# Power.net
KiCad netlist of a schematic drawn in Altium Designer
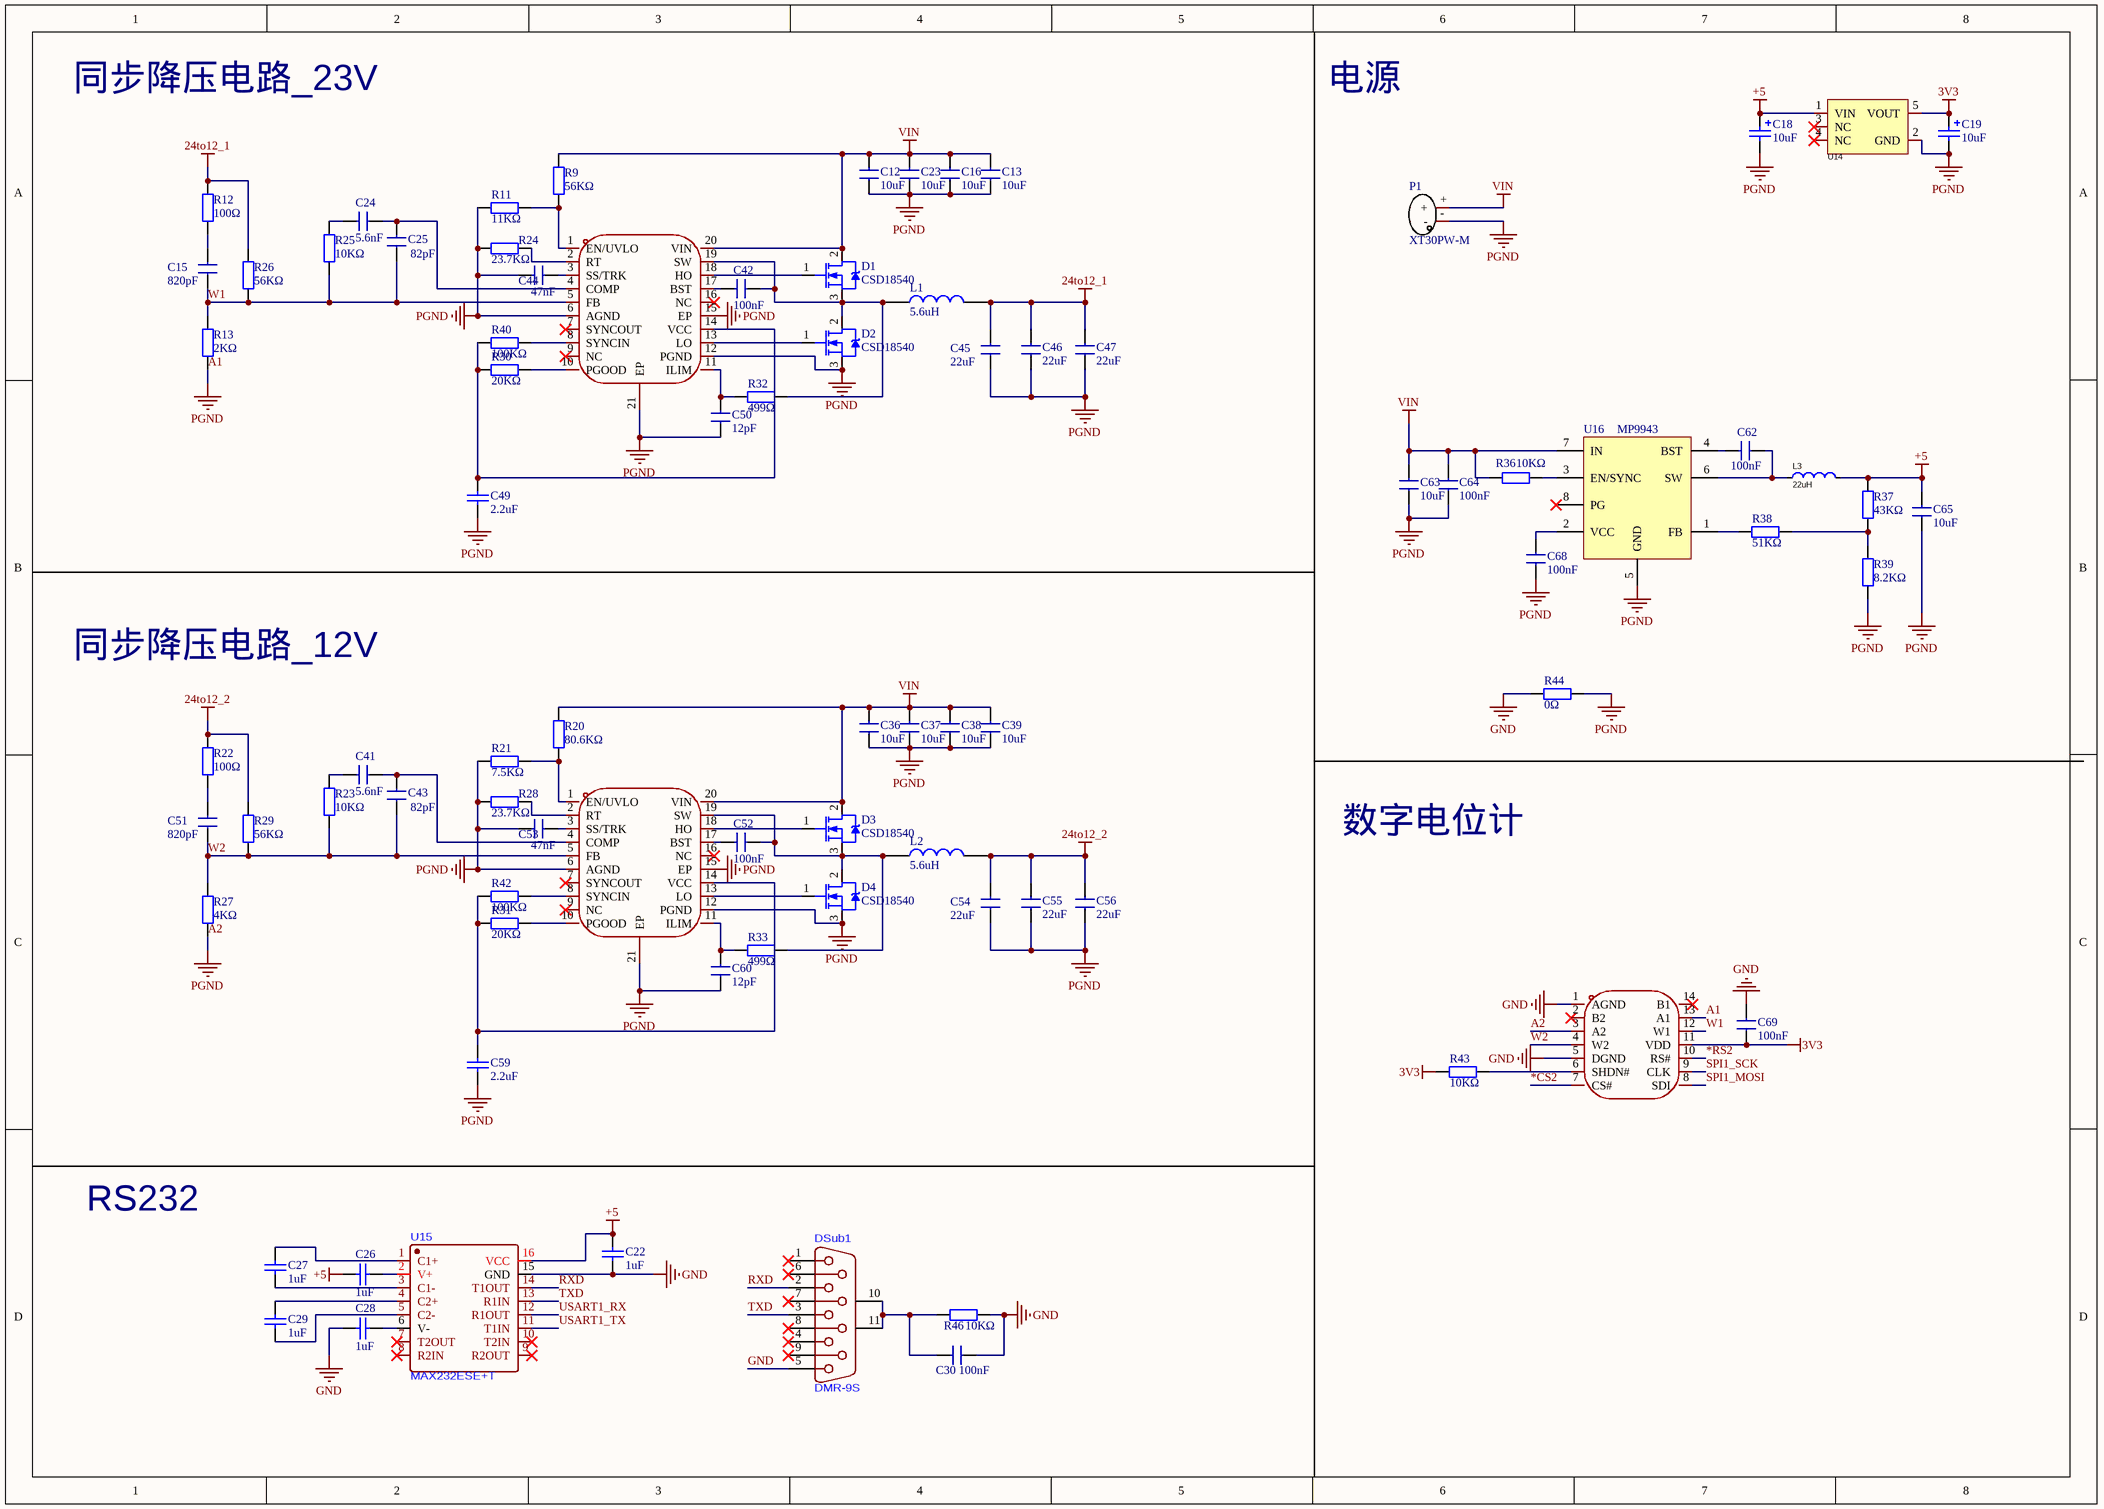
[diagram p0: Power.SchDoc]

(export (version "E")
  (design (tool "Eeschema 10.0.6"))
  (components
    (comp (ref "C12")
      (value "10uF")
      (footprint "1210")
      (description "1210贴片电容")
      (libsource (lib "Integrated_Library1") (part "1210贴片电容"))
    )
    (comp (ref "C13")
      (value "10uF")
      (footprint "1210")
      (description "1210贴片电容")
      (libsource (lib "En") (part "1210贴片电容"))
    )
    (comp (ref "C15")
      (value "820pF")
      (footprint "c0402")
      (description "贴片电容0402")
      (libsource (lib "Integrated_Library1") (part "0402贴片电容"))
    )
    (comp (ref "C16")
      (value "10uF")
      (footprint "1210")
      (description "1210贴片电容")
      (libsource (lib "En") (part "1210贴片电容"))
    )
    (comp (ref "C18")
      (value "10uF")
      (footprint "3216")
      (description "3216钽电容")
      (libsource (lib "Integrated_Library1") (part "3216钽电容"))
    )
    (comp (ref "C19")
      (value "10uF")
      (footprint "3216")
      (description "3216钽电容")
      (libsource (lib "Integrated_Library1") (part "3216钽电容"))
    )
    (comp (ref "C22")
      (value "1uF")
      (footprint "C 0603_M")
      (description "0603贴片电容")
      (libsource (lib "En") (part "0603贴片电容"))
    )
    (comp (ref "C23")
      (value "10uF")
      (footprint "1210")
      (description "1210贴片电容")
      (libsource (lib "En") (part "1210贴片电容"))
    )
    (comp (ref "C24")
      (value "5.6nF")
      (footprint "c0402")
      (description "贴片电容0402")
      (libsource (lib "Integrated_Library1") (part "0402贴片电容"))
    )
    (comp (ref "C25")
      (value "82pF")
      (footprint "c0402")
      (description "贴片电容0402")
      (libsource (lib "Integrated_Library1") (part "0402贴片电容"))
    )
    (comp (ref "C26")
      (value "1uF")
      (footprint "C 0603_M")
      (description "0603贴片电容")
      (libsource (lib "En") (part "0603贴片电容"))
    )
    (comp (ref "C27")
      (value "1uF")
      (footprint "C 0603_M")
      (description "0603贴片电容")
      (libsource (lib "En") (part "0603贴片电容"))
    )
    (comp (ref "C28")
      (value "1uF")
      (footprint "C 0603_M")
      (description "0603贴片电容")
      (libsource (lib "En") (part "0603贴片电容"))
    )
    (comp (ref "C29")
      (value "1uF")
      (footprint "C 0603_M")
      (description "0603贴片电容")
      (libsource (lib "En") (part "0603贴片电容"))
    )
    (comp (ref "C30")
      (value "100nF")
      (footprint "c0402")
      (description "贴片电容0402")
      (libsource (lib "Integrated_Library1") (part "0402贴片电容"))
    )
    (comp (ref "C36")
      (value "10uF")
      (footprint "1210")
      (description "1210贴片电容")
      (libsource (lib "Integrated_Library1") (part "1210贴片电容"))
    )
    (comp (ref "C37")
      (value "10uF")
      (footprint "1210")
      (description "1210贴片电容")
      (libsource (lib "En") (part "1210贴片电容"))
    )
    (comp (ref "C38")
      (value "10uF")
      (footprint "1210")
      (description "1210贴片电容")
      (libsource (lib "En") (part "1210贴片电容"))
    )
    (comp (ref "C39")
      (value "10uF")
      (footprint "1210")
      (description "1210贴片电容")
      (libsource (lib "En") (part "1210贴片电容"))
    )
    (comp (ref "C41")
      (value "5.6nF")
      (footprint "c0402")
      (description "贴片电容0402")
      (libsource (lib "Integrated_Library1") (part "0402贴片电容"))
    )
    (comp (ref "C42")
      (value "100nF")
      (footprint "C 0603_M")
      (description "贴片电容0402")
      (libsource (lib "Integrated_Library1") (part "0402贴片电容"))
    )
    (comp (ref "C43")
      (value "82pF")
      (footprint "c0402")
      (description "贴片电容0402")
      (libsource (lib "Integrated_Library1") (part "0402贴片电容"))
    )
    (comp (ref "C44")
      (value "47nF")
      (footprint "c0402")
      (description "贴片电容0402")
      (libsource (lib "Integrated_Library1") (part "0402贴片电容"))
    )
    (comp (ref "C45")
      (value "22uF")
      (footprint "1210")
      (description "1210贴片电容")
      (libsource (lib "En") (part "1210贴片电容"))
    )
    (comp (ref "C46")
      (value "22uF")
      (footprint "1210")
      (description "1210贴片电容")
      (libsource (lib "En") (part "1210贴片电容"))
    )
    (comp (ref "C47")
      (value "22uF")
      (footprint "1210")
      (description "1210贴片电容")
      (libsource (lib "En") (part "1210贴片电容"))
    )
    (comp (ref "C49")
      (value "2.2uF")
      (footprint "C 0603_M")
      (description "0603贴片电容")
      (libsource (lib "En") (part "0603贴片电容"))
    )
    (comp (ref "C50")
      (value "12pF")
      (footprint "c0402")
      (description "贴片电容0402")
      (libsource (lib "Integrated_Library1") (part "0402贴片电容"))
    )
    (comp (ref "C51")
      (value "820pF")
      (footprint "c0402")
      (description "贴片电容0402")
      (libsource (lib "Integrated_Library1") (part "0402贴片电容"))
    )
    (comp (ref "C52")
      (value "100nF")
      (footprint "C 0603_M")
      (description "贴片电容0402")
      (libsource (lib "Integrated_Library1") (part "0402贴片电容"))
    )
    (comp (ref "C53")
      (value "47nF")
      (footprint "c0402")
      (description "贴片电容0402")
      (libsource (lib "Integrated_Library1") (part "0402贴片电容"))
    )
    (comp (ref "C54")
      (value "22uF")
      (footprint "1210")
      (description "1210贴片电容")
      (libsource (lib "En") (part "1210贴片电容"))
    )
    (comp (ref "C55")
      (value "22uF")
      (footprint "1210")
      (description "1210贴片电容")
      (libsource (lib "En") (part "1210贴片电容"))
    )
    (comp (ref "C56")
      (value "22uF")
      (footprint "1210")
      (description "1210贴片电容")
      (libsource (lib "En") (part "1210贴片电容"))
    )
    (comp (ref "C59")
      (value "2.2uF")
      (footprint "C 0603_M")
      (description "0603贴片电容")
      (libsource (lib "En") (part "0603贴片电容"))
    )
    (comp (ref "C60")
      (value "12pF")
      (footprint "c0402")
      (description "贴片电容0402")
      (libsource (lib "Integrated_Library1") (part "0402贴片电容"))
    )
    (comp (ref "C62")
      (value "100nF")
      (footprint "c0402")
      (description "贴片电容0402")
      (libsource (lib "Integrated_Library1") (part "0402贴片电容"))
    )
    (comp (ref "C63")
      (value "10uF")
      (footprint "1210")
      (description "1210贴片电容")
      (libsource (lib "Integrated_Library1") (part "1210贴片电容"))
    )
    (comp (ref "C64")
      (value "100nF")
      (footprint "c0402")
      (description "贴片电容0402")
      (libsource (lib "Integrated_Library1") (part "0402贴片电容"))
    )
    (comp (ref "C65")
      (value "10uF")
      (footprint "1210")
      (description "1210贴片电容")
      (libsource (lib "Integrated_Library1") (part "1210贴片电容"))
    )
    (comp (ref "C68")
      (value "100nF")
      (footprint "c0402")
      (description "贴片电容0402")
      (libsource (lib "Integrated_Library1") (part "0402贴片电容"))
    )
    (comp (ref "C69")
      (value "100nF")
      (footprint "c0402")
      (description "贴片电容0402")
      (libsource (lib "Integrated_Library1") (part "0402贴片电容"))
    )
    (comp (ref "D1")
      (value "CSD18540")
      (footprint "pg-tdson-8")
      (description "N沟道MOS管")
      (fields (field (name "PUBLISHER") "Altium Limited"))
      (libsource (lib "En") (part "CSD18540"))
    )
    (comp (ref "D2")
      (value "CSD18540")
      (footprint "pg-tdson-8")
      (description "N沟道MOS管")
      (fields (field (name "PUBLISHER") "Altium Limited"))
      (libsource (lib "En") (part "CSD18540"))
    )
    (comp (ref "D3")
      (value "CSD18540")
      (footprint "pg-tdson-8")
      (description "N沟道MOS管")
      (fields (field (name "PUBLISHER") "Altium Limited"))
      (libsource (lib "En") (part "CSD18540"))
    )
    (comp (ref "D4")
      (value "CSD18540")
      (footprint "pg-tdson-8")
      (description "N沟道MOS管")
      (fields (field (name "PUBLISHER") "Altium Limited"))
      (libsource (lib "En") (part "CSD18540"))
    )
    (comp (ref "DSub1")
      (value "DMR-9S")
      (footprint "DSUB-TH_DMR-9S")
      (libsource (lib "Schlib1") (part "DMR-9S"))
    )
    (comp (ref "L1")
      (value "5.6uH")
      (footprint "L-SMD-0630")
      (description "一体成型屏蔽电感")
      (libsource (lib "En") (part "0630功率电感"))
    )
    (comp (ref "L2")
      (value "5.6uH")
      (footprint "L-SMD-0630")
      (description "一体成型屏蔽电感")
      (libsource (lib "En") (part "0630功率电感"))
    )
    (comp (ref "L3")
      (value "22uH")
      (footprint "IND-SMD_L5.4-W5.2")
      (description "一体成型屏蔽电感，0530封装，额定电流3A")
      (fields (field (name "MANUFACTURER") "XR(祥如)") (field (name "MANUFACTURER PART") "XR0530-100M"))
      (libsource (lib "En") (part "0530屏蔽电感"))
    )
    (comp (ref "P1")
      (value "XT30PW-M")
      (footprint "XT30PW-M")
      (description "卧式XT30母头")
      (fields (field (name "PUBLISHER") "Altium Limited"))
      (libsource (lib "Integrated_Library1") (part "卧式XT30母头"))
    )
    (comp (ref "R9")
      (value "56KΩ")
      (footprint "R0402")
      (description "0402贴片电阻")
      (libsource (lib "Integrated_Library1") (part "0402贴片电阻"))
    )
    (comp (ref "R11")
      (value "11KΩ")
      (footprint "R0402")
      (description "0402贴片电阻")
      (libsource (lib "") (part "0402贴片电阻_3"))
    )
    (comp (ref "R12")
      (value "100Ω")
      (footprint "R0402")
      (description "0402贴片电阻")
      (libsource (lib "") (part "0402贴片电阻_1"))
    )
    (comp (ref "R13")
      (value "2KΩ")
      (footprint "R0402")
      (description "0402贴片电阻")
      (libsource (lib "Integrated_Library1") (part "0402贴片电阻"))
    )
    (comp (ref "R20")
      (value "80.6KΩ")
      (footprint "R0402")
      (description "0402贴片电阻")
      (libsource (lib "Integrated_Library1") (part "0402贴片电阻"))
    )
    (comp (ref "R21")
      (value "7.5KΩ")
      (footprint "R0402")
      (description "0402贴片电阻")
      (libsource (lib "") (part "0402贴片电阻_3"))
    )
    (comp (ref "R22")
      (value "100Ω")
      (footprint "R0402")
      (description "0402贴片电阻")
      (libsource (lib "") (part "0402贴片电阻_1"))
    )
    (comp (ref "R23")
      (value "10KΩ")
      (footprint "R0402")
      (description "0402贴片电阻")
      (libsource (lib "") (part "0402贴片电阻_1"))
    )
    (comp (ref "R24")
      (value "23.7KΩ")
      (footprint "R0402")
      (description "0402贴片电阻")
      (libsource (lib "") (part "0402贴片电阻_2"))
    )
    (comp (ref "R25")
      (value "10KΩ")
      (footprint "R0402")
      (description "0402贴片电阻")
      (libsource (lib "") (part "0402贴片电阻_1"))
    )
    (comp (ref "R26")
      (value "56KΩ")
      (footprint "R0402")
      (description "0402贴片电阻")
      (libsource (lib "") (part "0402贴片电阻_1"))
    )
    (comp (ref "R27")
      (value "4KΩ")
      (footprint "R0402")
      (description "0402贴片电阻")
      (libsource (lib "Integrated_Library1") (part "0402贴片电阻"))
    )
    (comp (ref "R28")
      (value "23.7KΩ")
      (footprint "R0402")
      (description "0402贴片电阻")
      (libsource (lib "") (part "0402贴片电阻_2"))
    )
    (comp (ref "R29")
      (value "56KΩ")
      (footprint "R0402")
      (description "0402贴片电阻")
      (libsource (lib "") (part "0402贴片电阻_1"))
    )
    (comp (ref "R30")
      (value "20KΩ")
      (footprint "R0402")
      (description "0402贴片电阻")
      (libsource (lib "") (part "0402贴片电阻_2"))
    )
    (comp (ref "R31")
      (value "20KΩ")
      (footprint "R0402")
      (description "0402贴片电阻")
      (libsource (lib "") (part "0402贴片电阻_2"))
    )
    (comp (ref "R32")
      (value "499Ω")
      (footprint "R0402")
      (description "0402贴片电阻")
      (libsource (lib "") (part "0402贴片电阻_2"))
    )
    (comp (ref "R33")
      (value "499Ω")
      (footprint "R0402")
      (description "0402贴片电阻")
      (libsource (lib "") (part "0402贴片电阻_2"))
    )
    (comp (ref "R36")
      (value "10KΩ")
      (footprint "R0402")
      (description "0402贴片电阻")
      (libsource (lib "") (part "0402贴片电阻_3"))
    )
    (comp (ref "R37")
      (value "43KΩ")
      (footprint "R0402")
      (description "0402贴片电阻")
      (libsource (lib "") (part "0402贴片电阻_1"))
    )
    (comp (ref "R38")
      (value "51KΩ")
      (footprint "R0402")
      (description "0402贴片电阻")
      (libsource (lib "") (part "0402贴片电阻_3"))
    )
    (comp (ref "R39")
      (value "8.2KΩ")
      (footprint "R0402")
      (description "0402贴片电阻")
      (libsource (lib "") (part "0402贴片电阻_1"))
    )
    (comp (ref "R40")
      (value "100KΩ")
      (footprint "R0402")
      (description "0402贴片电阻")
      (libsource (lib "") (part "0402贴片电阻_2"))
    )
    (comp (ref "R42")
      (value "100KΩ")
      (footprint "R0402")
      (description "0402贴片电阻")
      (libsource (lib "") (part "0402贴片电阻_2"))
    )
    (comp (ref "R43")
      (value "10KΩ")
      (footprint "R0402")
      (description "0402贴片电阻")
      (libsource (lib "") (part "0402贴片电阻_2"))
    )
    (comp (ref "R44")
      (value "0Ω")
      (footprint "R0402")
      (description "0402贴片电阻")
      (libsource (lib "") (part "0402贴片电阻_3"))
    )
    (comp (ref "R46")
      (value "10KΩ")
      (footprint "R0402")
      (description "0402贴片电阻")
      (libsource (lib "") (part "0402贴片电阻_4"))
    )
    (comp (ref "U7")
      (value "LM25145RGYR")
      (footprint "VQFN-20_L4.5-W3.5-P0.50-BL-EP")
      (fields (field (name "MANUFACTURER") "TI(德州仪器)"))
      (libsource (lib "Schlib1") (part "LM25145RGYR"))
    )
    (comp (ref "U13")
      (value "LM25145RGYR")
      (footprint "VQFN-20_L4.5-W3.5-P0.50-BL-EP")
      (fields (field (name "MANUFACTURER") "TI(德州仪器)"))
      (libsource (lib "Schlib1") (part "LM25145RGYR"))
    )
    (comp (ref "U14")
      (value "XC6201P332MR-HXY")
      (footprint "SOT-23-5_L3.0-W1.7-P0.95-LS2.8-BR")
      (description "3.3V LDO")
      (fields (field (name "MANUFACTURER") "HXY MOSFET(华轩阳电子)"))
      (libsource (lib "Integrated_Library1") (part "XC6201P332MR-HXY"))
    )
    (comp (ref "U15")
      (value "MAX232ESE+T")
      (footprint "SOIC-16_L9.9-W3.9-P1.27-LS6.0-BL")
      (libsource (lib "Schlib1") (part "MAX232ESE+T"))
    )
    (comp (ref "U16")
      (value "MP9943")
      (footprint "QFN-8 3x3")
      (libsource (lib "Integrated_Library1") (part "MP9943"))
    )
    (comp (ref "U17")
      (value "AD8402ARZ10-REEL")
      (footprint "SOIC-14_L8.7-W3.9-P1.27-LS6.0-BL")
      (fields (field (name "MANUFACTURER") "ADI(亚德诺)"))
      (libsource (lib "Schlib1") (part "AD8402ARZ10-REEL"))
    )
  )
  (nets
    (net (code "1") (name "+5") (class "Default")
      (node (ref "C18") (pin "1") (pinfunction "1_1") (pintype "passive"))
      (node (ref "C22") (pin "2") (pinfunction "2_2") (pintype "passive"))
      (node (ref "C26") (pin "2") (pinfunction "2_2") (pintype "passive"))
      (node (ref "C65") (pin "2") (pinfunction "2_2") (pintype "passive"))
      (node (ref "L3") (pin "2") (pinfunction "2_2") (pintype "passive"))
      (node (ref "R37") (pin "2") (pinfunction "2_2") (pintype "passive"))
      (node (ref "U14") (pin "1") (pinfunction "VIN_1") (pintype "passive"))
      (node (ref "U15") (pin "16") (pinfunction "VCC_16") (pintype "passive"))
    )
    (net (code "2") (name "/*CS2") (class "Default")
      (node (ref "U17") (pin "7") (pinfunction "CS#_7") (pintype "passive"))
    )
    (net (code "3") (name "/*RS2") (class "Default")
      (node (ref "U17") (pin "10") (pinfunction "RS#_10") (pintype "passive"))
    )
    (net (code "4") (name "/RXD") (class "Default")
      (node (ref "DSub1") (pin "2") (pinfunction "2_2") (pintype "passive"))
      (node (ref "U15") (pin "14") (pinfunction "T1OUT_14") (pintype "passive"))
    )
    (net (code "5") (name "/SPI1_MOSI") (class "Default")
      (node (ref "U17") (pin "8") (pinfunction "SDI_8") (pintype "passive"))
    )
    (net (code "6") (name "/SPI1_SCK") (class "Default")
      (node (ref "U17") (pin "9") (pinfunction "CLK_9") (pintype "passive"))
    )
    (net (code "7") (name "/TXD") (class "Default")
      (node (ref "DSub1") (pin "3") (pinfunction "3_3") (pintype "passive"))
      (node (ref "U15") (pin "13") (pinfunction "R1IN_13") (pintype "passive"))
    )
    (net (code "8") (name "/USART1_RX") (class "Default")
      (node (ref "U15") (pin "12") (pinfunction "R1OUT_12") (pintype "passive"))
    )
    (net (code "9") (name "/USART1_TX") (class "Default")
      (node (ref "U15") (pin "11") (pinfunction "T1IN_11") (pintype "passive"))
    )
    (net (code "10") (name "/W1") (class "Default")
      (node (ref "C15") (pin "2") (pinfunction "2_2") (pintype "passive"))
      (node (ref "C25") (pin "1") (pinfunction "1_1") (pintype "passive"))
      (node (ref "R13") (pin "1") (pinfunction "1_1") (pintype "passive"))
      (node (ref "R25") (pin "1") (pinfunction "1_1") (pintype "passive"))
      (node (ref "R26") (pin "1") (pinfunction "1_1") (pintype "passive"))
      (node (ref "U13") (pin "5") (pinfunction "FB_5") (pintype "passive"))
      (node (ref "U17") (pin "12") (pinfunction "W1_12") (pintype "passive"))
    )
    (net (code "11") (name "/W2") (class "Default")
      (node (ref "C43") (pin "1") (pinfunction "1_1") (pintype "passive"))
      (node (ref "C51") (pin "2") (pinfunction "2_2") (pintype "passive"))
      (node (ref "R23") (pin "1") (pinfunction "1_1") (pintype "passive"))
      (node (ref "R27") (pin "1") (pinfunction "1_1") (pintype "passive"))
      (node (ref "R29") (pin "1") (pinfunction "1_1") (pintype "passive"))
      (node (ref "U17") (pin "4") (pinfunction "W2_4") (pintype "passive"))
      (node (ref "U7") (pin "5") (pinfunction "FB_5") (pintype "passive"))
    )
    (net (code "12") (name "3V3") (class "Default")
      (node (ref "C19") (pin "1") (pinfunction "1_1") (pintype "passive"))
      (node (ref "C69") (pin "2") (pinfunction "2_2") (pintype "passive"))
      (node (ref "R43") (pin "2") (pinfunction "2_2") (pintype "passive"))
      (node (ref "U14") (pin "5") (pinfunction "VOUT_5") (pintype "passive"))
      (node (ref "U17") (pin "11") (pinfunction "VDD_11") (pintype "passive"))
    )
    (net (code "13") (name "24to12_1") (class "Default")
      (node (ref "C45") (pin "2") (pinfunction "2_2") (pintype "passive"))
      (node (ref "C46") (pin "2") (pinfunction "2_2") (pintype "passive"))
      (node (ref "C47") (pin "2") (pinfunction "2_2") (pintype "passive"))
      (node (ref "L1") (pin "2") (pinfunction "2_2") (pintype "passive"))
      (node (ref "R12") (pin "2") (pinfunction "2_2") (pintype "passive"))
      (node (ref "R26") (pin "2") (pinfunction "2_2") (pintype "passive"))
    )
    (net (code "14") (name "24to12_2") (class "Default")
      (node (ref "C54") (pin "2") (pinfunction "2_2") (pintype "passive"))
      (node (ref "C55") (pin "2") (pinfunction "2_2") (pintype "passive"))
      (node (ref "C56") (pin "2") (pinfunction "2_2") (pintype "passive"))
      (node (ref "L2") (pin "2") (pinfunction "2_2") (pintype "passive"))
      (node (ref "R22") (pin "2") (pinfunction "2_2") (pintype "passive"))
      (node (ref "R29") (pin "2") (pinfunction "2_2") (pintype "passive"))
    )
    (net (code "15") (name "GND") (class "Default")
      (node (ref "C22") (pin "1") (pinfunction "1_1") (pintype "passive"))
      (node (ref "C28") (pin "2") (pinfunction "2_2") (pintype "passive"))
      (node (ref "C30") (pin "2") (pinfunction "2_2") (pintype "passive"))
      (node (ref "C69") (pin "1") (pinfunction "1_1") (pintype "passive"))
      (node (ref "DSub1") (pin "5") (pinfunction "5_5") (pintype "passive"))
      (node (ref "R44") (pin "1") (pinfunction "1_1") (pintype "passive"))
      (node (ref "R46") (pin "2") (pinfunction "2_2") (pintype "passive"))
      (node (ref "U15") (pin "15") (pinfunction "GND_15") (pintype "passive"))
      (node (ref "U17") (pin "1") (pinfunction "AGND_1") (pintype "passive"))
      (node (ref "U17") (pin "5") (pinfunction "DGND_5") (pintype "passive"))
    )
    (net (code "16") (name "Net-(C15-Pad1)") (class "Default")
      (node (ref "C15") (pin "1") (pinfunction "1_1") (pintype "passive"))
      (node (ref "R12") (pin "1") (pinfunction "1_1") (pintype "passive"))
    )
    (net (code "17") (name "Net-(C24-Pad2)") (class "Default")
      (node (ref "C24") (pin "2") (pinfunction "2_2") (pintype "passive"))
      (node (ref "R25") (pin "2") (pinfunction "2_2") (pintype "passive"))
    )
    (net (code "18") (name "Net-(C41-Pad2)") (class "Default")
      (node (ref "C41") (pin "2") (pinfunction "2_2") (pintype "passive"))
      (node (ref "R23") (pin "2") (pinfunction "2_2") (pintype "passive"))
    )
    (net (code "19") (name "Net-(C51-Pad1)") (class "Default")
      (node (ref "C51") (pin "1") (pinfunction "1_1") (pintype "passive"))
      (node (ref "R22") (pin "1") (pinfunction "1_1") (pintype "passive"))
    )
    (net (code "20") (name "Net-(D1-G)") (class "Default")
      (node (ref "D1") (pin "1") (pinfunction "G_1") (pintype "passive"))
      (node (ref "U13") (pin "18") (pinfunction "HO_18") (pintype "passive"))
    )
    (net (code "21") (name "Net-(D1-S)") (class "Default")
      (node (ref "C42") (pin "1") (pinfunction "1_1") (pintype "passive"))
      (node (ref "D1") (pin "3") (pinfunction "S_3") (pintype "passive"))
      (node (ref "D2") (pin "2") (pinfunction "D_2") (pintype "passive"))
      (node (ref "L1") (pin "1") (pinfunction "1_1") (pintype "passive"))
      (node (ref "R32") (pin "1") (pinfunction "1_1") (pintype "passive"))
      (node (ref "U13") (pin "19") (pinfunction "SW_19") (pintype "passive"))
    )
    (net (code "22") (name "Net-(D2-G)") (class "Default")
      (node (ref "D2") (pin "1") (pinfunction "G_1") (pintype "passive"))
      (node (ref "U13") (pin "13") (pinfunction "LO_13") (pintype "passive"))
    )
    (net (code "23") (name "Net-(D3-G)") (class "Default")
      (node (ref "D3") (pin "1") (pinfunction "G_1") (pintype "passive"))
      (node (ref "U7") (pin "18") (pinfunction "HO_18") (pintype "passive"))
    )
    (net (code "24") (name "Net-(D3-S)") (class "Default")
      (node (ref "C52") (pin "1") (pinfunction "1_1") (pintype "passive"))
      (node (ref "D3") (pin "3") (pinfunction "S_3") (pintype "passive"))
      (node (ref "D4") (pin "2") (pinfunction "D_2") (pintype "passive"))
      (node (ref "L2") (pin "1") (pinfunction "1_1") (pintype "passive"))
      (node (ref "R33") (pin "1") (pinfunction "1_1") (pintype "passive"))
      (node (ref "U7") (pin "19") (pinfunction "SW_19") (pintype "passive"))
    )
    (net (code "25") (name "Net-(D4-G)") (class "Default")
      (node (ref "D4") (pin "1") (pinfunction "G_1") (pintype "passive"))
      (node (ref "U7") (pin "13") (pinfunction "LO_13") (pintype "passive"))
    )
    (net (code "26") (name "Net-(DSub1-MH1)") (class "Default")
      (node (ref "C30") (pin "1") (pinfunction "1_1") (pintype "passive"))
      (node (ref "DSub1") (pin "10") (pinfunction "MH1_10") (pintype "passive"))
      (node (ref "DSub1") (pin "11") (pinfunction "MH2_11") (pintype "passive"))
      (node (ref "R46") (pin "1") (pinfunction "1_1") (pintype "passive"))
    )
    (net (code "27") (name "Net-(R37-Pad1)") (class "Default")
      (node (ref "R37") (pin "1") (pinfunction "1_1") (pintype "passive"))
      (node (ref "R38") (pin "2") (pinfunction "2_2") (pintype "passive"))
      (node (ref "R39") (pin "2") (pinfunction "2_2") (pintype "passive"))
    )
    (net (code "28") (name "Net-(U7-BST)") (class "Default")
      (node (ref "C52") (pin "2") (pinfunction "2_2") (pintype "passive"))
      (node (ref "U7") (pin "17") (pinfunction "BST_17") (pintype "passive"))
    )
    (net (code "29") (name "Net-(U7-COMP)") (class "Default")
      (node (ref "C41") (pin "1") (pinfunction "1_1") (pintype "passive"))
      (node (ref "C43") (pin "2") (pinfunction "2_2") (pintype "passive"))
      (node (ref "U7") (pin "4") (pinfunction "COMP_4") (pintype "passive"))
    )
    (net (code "30") (name "Net-(U7-EN{slash}UVLO)") (class "Default")
      (node (ref "R20") (pin "2") (pinfunction "2_2") (pintype "passive"))
      (node (ref "R21") (pin "2") (pinfunction "2_2") (pintype "passive"))
      (node (ref "U7") (pin "1") (pinfunction "EN/UVLO_1") (pintype "passive"))
    )
    (net (code "31") (name "Net-(U7-ILIM)") (class "Default")
      (node (ref "C60") (pin "2") (pinfunction "2_2") (pintype "passive"))
      (node (ref "R33") (pin "2") (pinfunction "2_2") (pintype "passive"))
      (node (ref "U7") (pin "11") (pinfunction "ILIM_11") (pintype "passive"))
    )
    (net (code "32") (name "Net-(U7-PGOOD)") (class "Default")
      (node (ref "R31") (pin "1") (pinfunction "1_1") (pintype "passive"))
      (node (ref "U7") (pin "10") (pinfunction "PGOOD_10") (pintype "passive"))
    )
    (net (code "33") (name "Net-(U7-RT)") (class "Default")
      (node (ref "R28") (pin "1") (pinfunction "1_1") (pintype "passive"))
      (node (ref "U7") (pin "2") (pinfunction "RT_2") (pintype "passive"))
    )
    (net (code "34") (name "Net-(U7-SS{slash}TRK)") (class "Default")
      (node (ref "C53") (pin "1") (pinfunction "1_1") (pintype "passive"))
      (node (ref "U7") (pin "3") (pinfunction "SS/TRK_3") (pintype "passive"))
    )
    (net (code "35") (name "Net-(U7-SYNCIN)") (class "Default")
      (node (ref "R42") (pin "1") (pinfunction "1_1") (pintype "passive"))
      (node (ref "U7") (pin "8") (pinfunction "SYNCIN_8") (pintype "passive"))
    )
    (net (code "36") (name "Net-(U7-VCC)") (class "Default")
      (node (ref "C59") (pin "2") (pinfunction "2_2") (pintype "passive"))
      (node (ref "R31") (pin "2") (pinfunction "2_2") (pintype "passive"))
      (node (ref "R42") (pin "2") (pinfunction "2_2") (pintype "passive"))
      (node (ref "U7") (pin "14") (pinfunction "VCC_14") (pintype "passive"))
    )
    (net (code "37") (name "Net-(U13-BST)") (class "Default")
      (node (ref "C42") (pin "2") (pinfunction "2_2") (pintype "passive"))
      (node (ref "U13") (pin "17") (pinfunction "BST_17") (pintype "passive"))
    )
    (net (code "38") (name "Net-(U13-COMP)") (class "Default")
      (node (ref "C24") (pin "1") (pinfunction "1_1") (pintype "passive"))
      (node (ref "C25") (pin "2") (pinfunction "2_2") (pintype "passive"))
      (node (ref "U13") (pin "4") (pinfunction "COMP_4") (pintype "passive"))
    )
    (net (code "39") (name "Net-(U13-EN{slash}UVLO)") (class "Default")
      (node (ref "R11") (pin "2") (pinfunction "2_2") (pintype "passive"))
      (node (ref "R9") (pin "2") (pinfunction "2_2") (pintype "passive"))
      (node (ref "U13") (pin "1") (pinfunction "EN/UVLO_1") (pintype "passive"))
    )
    (net (code "40") (name "Net-(U13-ILIM)") (class "Default")
      (node (ref "C50") (pin "2") (pinfunction "2_2") (pintype "passive"))
      (node (ref "R32") (pin "2") (pinfunction "2_2") (pintype "passive"))
      (node (ref "U13") (pin "11") (pinfunction "ILIM_11") (pintype "passive"))
    )
    (net (code "41") (name "Net-(U13-PGOOD)") (class "Default")
      (node (ref "R30") (pin "1") (pinfunction "1_1") (pintype "passive"))
      (node (ref "U13") (pin "10") (pinfunction "PGOOD_10") (pintype "passive"))
    )
    (net (code "42") (name "Net-(U13-RT)") (class "Default")
      (node (ref "R24") (pin "1") (pinfunction "1_1") (pintype "passive"))
      (node (ref "U13") (pin "2") (pinfunction "RT_2") (pintype "passive"))
    )
    (net (code "43") (name "Net-(U13-SS{slash}TRK)") (class "Default")
      (node (ref "C44") (pin "1") (pinfunction "1_1") (pintype "passive"))
      (node (ref "U13") (pin "3") (pinfunction "SS/TRK_3") (pintype "passive"))
    )
    (net (code "44") (name "Net-(U13-SYNCIN)") (class "Default")
      (node (ref "R40") (pin "1") (pinfunction "1_1") (pintype "passive"))
      (node (ref "U13") (pin "8") (pinfunction "SYNCIN_8") (pintype "passive"))
    )
    (net (code "45") (name "Net-(U13-VCC)") (class "Default")
      (node (ref "C49") (pin "2") (pinfunction "2_2") (pintype "passive"))
      (node (ref "R30") (pin "2") (pinfunction "2_2") (pintype "passive"))
      (node (ref "R40") (pin "2") (pinfunction "2_2") (pintype "passive"))
      (node (ref "U13") (pin "14") (pinfunction "VCC_14") (pintype "passive"))
    )
    (net (code "46") (name "Net-(U15-C1+)") (class "Default")
      (node (ref "C27") (pin "1") (pinfunction "1_1") (pintype "passive"))
      (node (ref "U15") (pin "1") (pinfunction "C1+_1") (pintype "passive"))
    )
    (net (code "47") (name "Net-(U15-C1-)") (class "Default")
      (node (ref "C27") (pin "2") (pinfunction "2_2") (pintype "passive"))
      (node (ref "U15") (pin "3") (pinfunction "C1-_3") (pintype "passive"))
    )
    (net (code "48") (name "Net-(U15-C2+)") (class "Default")
      (node (ref "C29") (pin "1") (pinfunction "1_1") (pintype "passive"))
      (node (ref "U15") (pin "4") (pinfunction "C2+_4") (pintype "passive"))
    )
    (net (code "49") (name "Net-(U15-C2-)") (class "Default")
      (node (ref "C29") (pin "2") (pinfunction "2_2") (pintype "passive"))
      (node (ref "U15") (pin "5") (pinfunction "C2-_5") (pintype "passive"))
    )
    (net (code "50") (name "Net-(U15-V+)") (class "Default")
      (node (ref "C26") (pin "1") (pinfunction "1_1") (pintype "passive"))
      (node (ref "U15") (pin "2") (pinfunction "V+_2") (pintype "passive"))
    )
    (net (code "51") (name "Net-(U15-V-)") (class "Default")
      (node (ref "C28") (pin "1") (pinfunction "1_1") (pintype "passive"))
      (node (ref "U15") (pin "6") (pinfunction "V-_6") (pintype "passive"))
    )
    (net (code "52") (name "Net-(U16-BST)") (class "Default")
      (node (ref "C62") (pin "1") (pinfunction "1_1") (pintype "passive"))
      (node (ref "U16") (pin "4") (pinfunction "BST_4") (pintype "passive"))
    )
    (net (code "53") (name "Net-(U16-EN{slash}SYNC)") (class "Default")
      (node (ref "R36") (pin "2") (pinfunction "2_2") (pintype "passive"))
      (node (ref "U16") (pin "3") (pinfunction "EN/SYNC_3") (pintype "passive"))
    )
    (net (code "54") (name "Net-(U16-FB)") (class "Default")
      (node (ref "R38") (pin "1") (pinfunction "1_1") (pintype "passive"))
      (node (ref "U16") (pin "1") (pinfunction "FB_1") (pintype "passive"))
    )
    (net (code "55") (name "Net-(U16-SW)") (class "Default")
      (node (ref "C62") (pin "2") (pinfunction "2_2") (pintype "passive"))
      (node (ref "L3") (pin "1") (pinfunction "1_1") (pintype "passive"))
      (node (ref "U16") (pin "6") (pinfunction "SW_6") (pintype "passive"))
    )
    (net (code "56") (name "Net-(U16-VCC)") (class "Default")
      (node (ref "C68") (pin "2") (pinfunction "2_2") (pintype "passive"))
      (node (ref "U16") (pin "2") (pinfunction "VCC_2") (pintype "passive"))
    )
    (net (code "57") (name "Net-(U17-SHDN#)") (class "Default")
      (node (ref "R43") (pin "1") (pinfunction "1_1") (pintype "passive"))
      (node (ref "U17") (pin "6") (pinfunction "SHDN#_6") (pintype "passive"))
    )
    (net (code "58") (name "PGND") (class "Default")
      (node (ref "C12") (pin "1") (pinfunction "1_1") (pintype "passive"))
      (node (ref "C13") (pin "1") (pinfunction "1_1") (pintype "passive"))
      (node (ref "C16") (pin "1") (pinfunction "1_1") (pintype "passive"))
      (node (ref "C18") (pin "2") (pinfunction "2_2") (pintype "passive"))
      (node (ref "C19") (pin "2") (pinfunction "2_2") (pintype "passive"))
      (node (ref "C23") (pin "1") (pinfunction "1_1") (pintype "passive"))
      (node (ref "C36") (pin "1") (pinfunction "1_1") (pintype "passive"))
      (node (ref "C37") (pin "1") (pinfunction "1_1") (pintype "passive"))
      (node (ref "C38") (pin "1") (pinfunction "1_1") (pintype "passive"))
      (node (ref "C39") (pin "1") (pinfunction "1_1") (pintype "passive"))
      (node (ref "C44") (pin "2") (pinfunction "2_2") (pintype "passive"))
      (node (ref "C45") (pin "1") (pinfunction "1_1") (pintype "passive"))
      (node (ref "C46") (pin "1") (pinfunction "1_1") (pintype "passive"))
      (node (ref "C47") (pin "1") (pinfunction "1_1") (pintype "passive"))
      (node (ref "C49") (pin "1") (pinfunction "1_1") (pintype "passive"))
      (node (ref "C50") (pin "1") (pinfunction "1_1") (pintype "passive"))
      (node (ref "C53") (pin "2") (pinfunction "2_2") (pintype "passive"))
      (node (ref "C54") (pin "1") (pinfunction "1_1") (pintype "passive"))
      (node (ref "C55") (pin "1") (pinfunction "1_1") (pintype "passive"))
      (node (ref "C56") (pin "1") (pinfunction "1_1") (pintype "passive"))
      (node (ref "C59") (pin "1") (pinfunction "1_1") (pintype "passive"))
      (node (ref "C60") (pin "1") (pinfunction "1_1") (pintype "passive"))
      (node (ref "C63") (pin "1") (pinfunction "1_1") (pintype "passive"))
      (node (ref "C64") (pin "1") (pinfunction "1_1") (pintype "passive"))
      (node (ref "C65") (pin "1") (pinfunction "1_1") (pintype "passive"))
      (node (ref "C68") (pin "1") (pinfunction "1_1") (pintype "passive"))
      (node (ref "D2") (pin "3") (pinfunction "S_3") (pintype "passive"))
      (node (ref "D4") (pin "3") (pinfunction "S_3") (pintype "passive"))
      (node (ref "P1") (pin "-") (pinfunction "-_-") (pintype "passive"))
      (node (ref "R11") (pin "1") (pinfunction "1_1") (pintype "passive"))
      (node (ref "R13") (pin "2") (pinfunction "2_2") (pintype "passive"))
      (node (ref "R21") (pin "1") (pinfunction "1_1") (pintype "passive"))
      (node (ref "R24") (pin "2") (pinfunction "2_2") (pintype "passive"))
      (node (ref "R27") (pin "2") (pinfunction "2_2") (pintype "passive"))
      (node (ref "R28") (pin "2") (pinfunction "2_2") (pintype "passive"))
      (node (ref "R39") (pin "1") (pinfunction "1_1") (pintype "passive"))
      (node (ref "R44") (pin "2") (pinfunction "2_2") (pintype "passive"))
      (node (ref "U13") (pin "12") (pinfunction "PGND_12") (pintype "passive"))
      (node (ref "U13") (pin "15") (pinfunction "EP_15") (pintype "passive"))
      (node (ref "U13") (pin "21") (pinfunction "EP_21") (pintype "passive"))
      (node (ref "U13") (pin "6") (pinfunction "AGND_6") (pintype "passive"))
      (node (ref "U14") (pin "2") (pinfunction "GND_2") (pintype "passive"))
      (node (ref "U16") (pin "5") (pinfunction "GND_5") (pintype "passive"))
      (node (ref "U17") (pin "13") (pinfunction "A1_13") (pintype "passive"))
      (node (ref "U17") (pin "3") (pinfunction "A2_3") (pintype "passive"))
      (node (ref "U7") (pin "12") (pinfunction "PGND_12") (pintype "passive"))
      (node (ref "U7") (pin "15") (pinfunction "EP_15") (pintype "passive"))
      (node (ref "U7") (pin "21") (pinfunction "EP_21") (pintype "passive"))
      (node (ref "U7") (pin "6") (pinfunction "AGND_6") (pintype "passive"))
    )
    (net (code "59") (name "VIN") (class "Default")
      (node (ref "C12") (pin "2") (pinfunction "2_2") (pintype "passive"))
      (node (ref "C13") (pin "2") (pinfunction "2_2") (pintype "passive"))
      (node (ref "C16") (pin "2") (pinfunction "2_2") (pintype "passive"))
      (node (ref "C23") (pin "2") (pinfunction "2_2") (pintype "passive"))
      (node (ref "C36") (pin "2") (pinfunction "2_2") (pintype "passive"))
      (node (ref "C37") (pin "2") (pinfunction "2_2") (pintype "passive"))
      (node (ref "C38") (pin "2") (pinfunction "2_2") (pintype "passive"))
      (node (ref "C39") (pin "2") (pinfunction "2_2") (pintype "passive"))
      (node (ref "C63") (pin "2") (pinfunction "2_2") (pintype "passive"))
      (node (ref "C64") (pin "2") (pinfunction "2_2") (pintype "passive"))
      (node (ref "D1") (pin "2") (pinfunction "D_2") (pintype "passive"))
      (node (ref "D3") (pin "2") (pinfunction "D_2") (pintype "passive"))
      (node (ref "P1") (pin "+") (pinfunction "+_+") (pintype "passive"))
      (node (ref "R20") (pin "1") (pinfunction "1_1") (pintype "passive"))
      (node (ref "R36") (pin "1") (pinfunction "1_1") (pintype "passive"))
      (node (ref "R9") (pin "1") (pinfunction "1_1") (pintype "passive"))
      (node (ref "U13") (pin "20") (pinfunction "VIN_20") (pintype "passive"))
      (node (ref "U16") (pin "7") (pinfunction "IN_7") (pintype "passive"))
      (node (ref "U7") (pin "20") (pinfunction "VIN_20") (pintype "passive"))
    )
    (net (code "60") (name "unconnected-(DSub1-Pad1)") (class "Default")
      (node (ref "DSub1") (pin "1") (pinfunction "1_1") (pintype "passive+no_connect"))
    )
    (net (code "61") (name "unconnected-(DSub1-Pad4)") (class "Default")
      (node (ref "DSub1") (pin "4") (pinfunction "4_4") (pintype "passive+no_connect"))
    )
    (net (code "62") (name "unconnected-(DSub1-Pad6)") (class "Default")
      (node (ref "DSub1") (pin "6") (pinfunction "6_6") (pintype "passive+no_connect"))
    )
    (net (code "63") (name "unconnected-(DSub1-Pad7)") (class "Default")
      (node (ref "DSub1") (pin "7") (pinfunction "7_7") (pintype "passive+no_connect"))
    )
    (net (code "64") (name "unconnected-(DSub1-Pad8)") (class "Default")
      (node (ref "DSub1") (pin "8") (pinfunction "8_8") (pintype "passive+no_connect"))
    )
    (net (code "65") (name "unconnected-(DSub1-Pad9)") (class "Default")
      (node (ref "DSub1") (pin "9") (pinfunction "9_9") (pintype "passive+no_connect"))
    )
    (net (code "66") (name "unconnected-(U7-NC-Pad9)") (class "Default")
      (node (ref "U7") (pin "9") (pinfunction "NC_9") (pintype "passive+no_connect"))
    )
    (net (code "67") (name "unconnected-(U7-NC-Pad16)") (class "Default")
      (node (ref "U7") (pin "16") (pinfunction "NC_16") (pintype "passive+no_connect"))
    )
    (net (code "68") (name "unconnected-(U7-SYNCOUT-Pad7)") (class "Default")
      (node (ref "U7") (pin "7") (pinfunction "SYNCOUT_7") (pintype "passive+no_connect"))
    )
    (net (code "69") (name "unconnected-(U13-NC-Pad9)") (class "Default")
      (node (ref "U13") (pin "9") (pinfunction "NC_9") (pintype "passive+no_connect"))
    )
    (net (code "70") (name "unconnected-(U13-NC-Pad16)") (class "Default")
      (node (ref "U13") (pin "16") (pinfunction "NC_16") (pintype "passive+no_connect"))
    )
    (net (code "71") (name "unconnected-(U13-SYNCOUT-Pad7)") (class "Default")
      (node (ref "U13") (pin "7") (pinfunction "SYNCOUT_7") (pintype "passive+no_connect"))
    )
    (net (code "72") (name "unconnected-(U14-NC-Pad3)") (class "Default")
      (node (ref "U14") (pin "3") (pinfunction "NC_3") (pintype "passive+no_connect"))
    )
    (net (code "73") (name "unconnected-(U14-NC-Pad4)") (class "Default")
      (node (ref "U14") (pin "4") (pinfunction "NC_4") (pintype "passive+no_connect"))
    )
    (net (code "74") (name "unconnected-(U15-R2IN-Pad8)") (class "Default")
      (node (ref "U15") (pin "8") (pinfunction "R2IN_8") (pintype "passive+no_connect"))
    )
    (net (code "75") (name "unconnected-(U15-R2OUT-Pad9)") (class "Default")
      (node (ref "U15") (pin "9") (pinfunction "R2OUT_9") (pintype "passive+no_connect"))
    )
    (net (code "76") (name "unconnected-(U15-T2IN-Pad10)") (class "Default")
      (node (ref "U15") (pin "10") (pinfunction "T2IN_10") (pintype "passive+no_connect"))
    )
    (net (code "77") (name "unconnected-(U15-T2OUT-Pad7)") (class "Default")
      (node (ref "U15") (pin "7") (pinfunction "T2OUT_7") (pintype "passive+no_connect"))
    )
    (net (code "78") (name "unconnected-(U16-PG-Pad8)") (class "Default")
      (node (ref "U16") (pin "8") (pinfunction "PG_8") (pintype "passive+no_connect"))
    )
    (net (code "79") (name "unconnected-(U17-B1-Pad14)") (class "Default")
      (node (ref "U17") (pin "14") (pinfunction "B1_14") (pintype "passive+no_connect"))
    )
    (net (code "80") (name "unconnected-(U17-B2-Pad2)") (class "Default")
      (node (ref "U17") (pin "2") (pinfunction "B2_2") (pintype "passive+no_connect"))
    )
  )
)
